# Power_Supply.net
KiCad netlist of a schematic drawn in Altium Designer
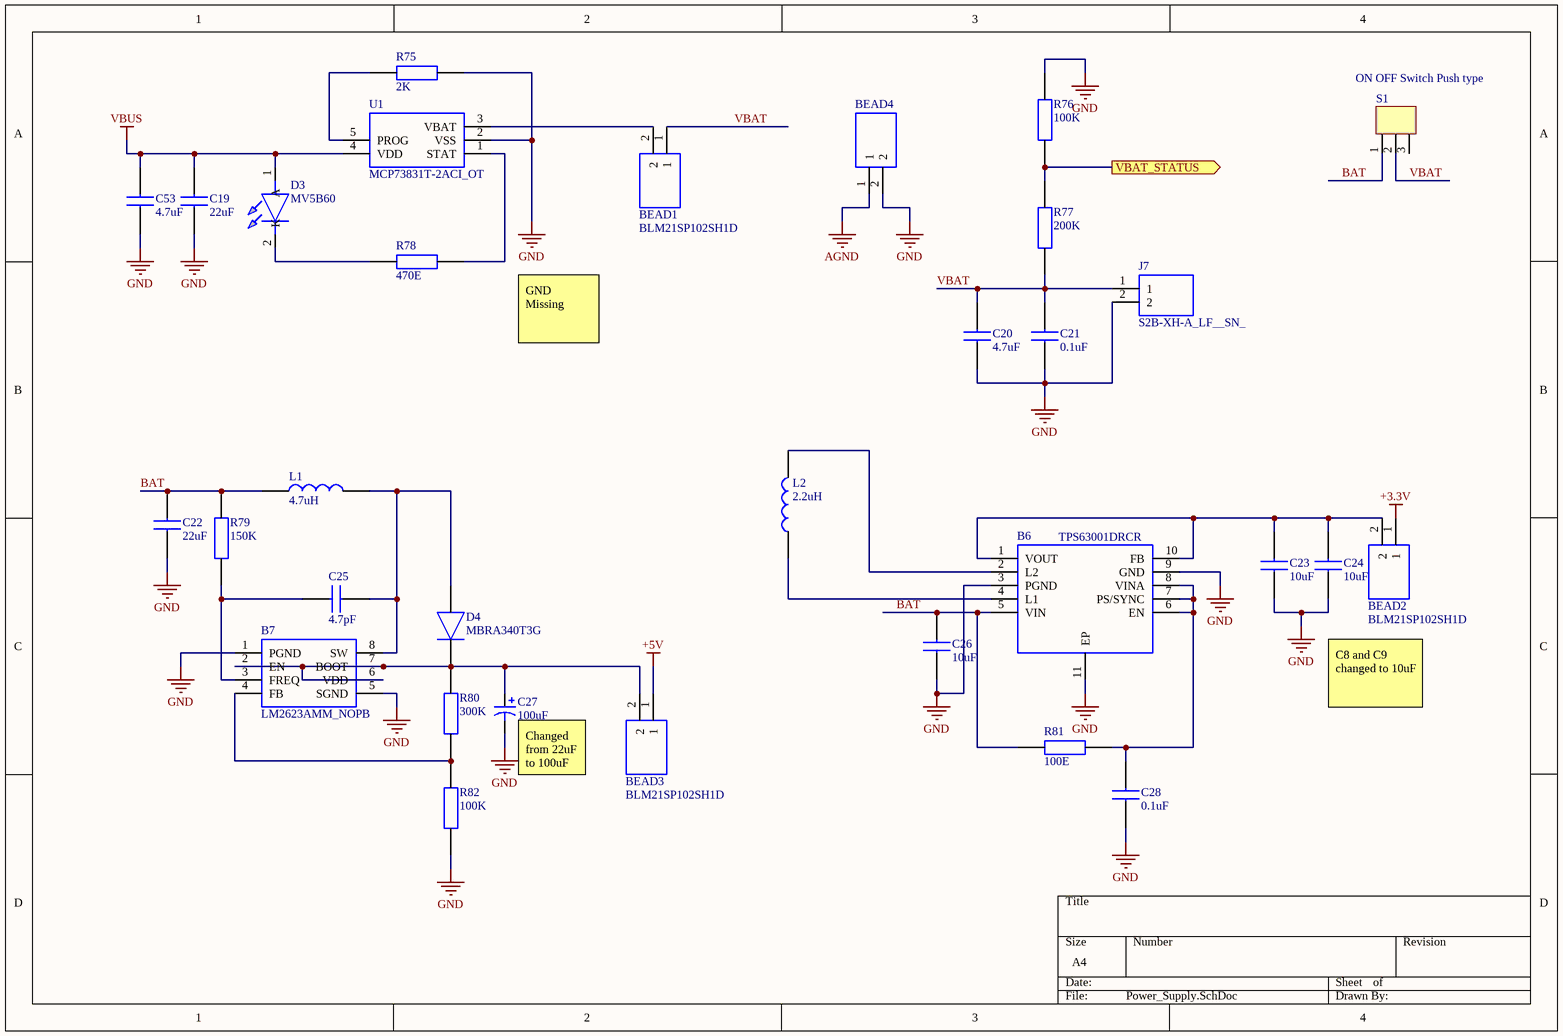
[diagram p0: Power_Supply.SchDoc]

(export (version "E")
  (design (tool "Eeschema 10.0.6"))
  (components
    (comp (ref "B6")
      (value "TPS63001DRCR")
      (footprint "SON50P300X300X100-11N-D")
      (description "96% Buck-Boost Converter with 1.7A Current Switches, 3.3V fixed Output voltage in 3x3 QFN")
      (fields (field (name "MOUSER PART NUMBER") "595-TPS63001DRCR"))
      (libsource (lib "TPS63001DRCR") (part "TPS63001DRCR"))
    )
    (comp (ref "B7")
      (value "LM2623AMM_NOPB")
      (footprint "SOP65P490X110-8N")
      (description "General Purpose, Gated Oscillator Based, DC/DC Boost Converter")
      (fields
        (field (name "MANUFACTURER_PART_NUMBER") "LM2623AMM/NOPB")
        (field (name "MOUSER PART NUMBER") "926-LM2623AMM/NOPB")
      )
      (libsource (lib "LM2623AMM") (part "LM2623AMM_NOPB"))
    )
    (comp (ref "BEAD1")
      (value "BLM21SP102SH1D")
      (footprint "Bead_0805")
      (description "BLM21_H1D Series EMI Suppression Filter 1000+/-25% at 100MHz 1.6A @85")
      (fields (field (name "MOUSER PART NUMBER") "81-BLM21SP102SH1D"))
      (libsource (lib "Bead_0805") (part "BLM21SP102SH1D"))
    )
    (comp (ref "BEAD2")
      (value "BLM21SP102SH1D")
      (footprint "Bead_0805")
      (description "BLM21_H1D Series EMI Suppression Filter 1000+/-25% at 100MHz 1.6A @85")
      (fields (field (name "MOUSER PART NUMBER") "81-BLM21SP102SH1D"))
      (libsource (lib "Bead_0805") (part "BLM21SP102SH1D"))
    )
    (comp (ref "BEAD3")
      (value "BLM21SP102SH1D")
      (footprint "Bead_0805")
      (description "BLM21_H1D Series EMI Suppression Filter 1000+/-25% at 100MHz 1.6A @85")
      (fields (field (name "MOUSER PART NUMBER") "81-BLM21SP102SH1D"))
      (libsource (lib "Bead_0805") (part "BLM21SP102SH1D"))
    )
    (comp (ref "BEAD4")
      (value "BLM21SP102SH1D")
      (footprint "Bead_0805")
      (description "BLM21_H1D Series EMI Suppression Filter 1000+/-25% at 100MHz 1.6A @85")
      (fields (field (name "MOUSER PART NUMBER") "81-BLM21SP102SH1D"))
      (libsource (lib "Bead_0805") (part "BLM21SP102SH1D"))
    )
    (comp (ref "C19")
      (value "22uF")
      (footprint "CAPC3216X180N")
      (description "Multilayer Ceramic Capacitors MLCC - SMD/SMT 22uF 10% 10V")
      (fields
        (field (name "MANUFACTURER_PART_NUMBER") "CC1206KKX7R6BB226")
        (field (name "MOUSER PART NUMBER") "603-CC206KKX7R6BB226")
      )
      (libsource (lib "22uF_1206") (part "CC1206KKX7R6BB226"))
    )
    (comp (ref "C20")
      (value "4.7uF")
      (footprint "CAPC2012X140N")
      (description "KEMET 0805 (2012M) 4.7uF MLCC 6.3V dc +/-5% SMD C0805C475J9RACAUTO")
      (fields
        (field (name "MANUFACTURER_PART_NUMBER") "C0805C475J9RACAUTO")
        (field (name "MOUSER PART NUMBER") "80-C0805C475J9RAUTO")
      )
      (libsource (lib "4.7uF_0805") (part "C0805C475J9RACAUTO"))
    )
    (comp (ref "C21")
      (value "0.1uF")
      (footprint "CAPC1005X55N")
      (description "Multilayer Ceramic Capacitors MLCC - SMD/SMT 16V 0.1uF X7R 0402 20%")
      (fields
        (field (name "MANUFACTURER_PART_NUMBER") "C0402C104M4RECTU")
        (field (name "MOUSER PART NUMBER") "80-C0402C104M4RECTU")
      )
      (libsource (lib "0.1uF_0402") (part "C0402C104M4RECTU"))
    )
    (comp (ref "C22")
      (value "22uF")
      (footprint "CAPC3216X180N")
      (description "Multilayer Ceramic Capacitors MLCC - SMD/SMT 22uF 10% 10V")
      (fields
        (field (name "MANUFACTURER_PART_NUMBER") "CC1206KKX7R6BB226")
        (field (name "MOUSER PART NUMBER") "603-CC206KKX7R6BB226")
      )
      (libsource (lib "22uF_1206") (part "CC1206KKX7R6BB226"))
    )
    (comp (ref "C23")
      (value "10uF")
      (footprint "CAPC1608X80N")
      (description "CAP TANT 10UF 10% 6.3V 1206")
      (fields
        (field (name "MANUFACTURER_PART_NUMBER") "293D106X96R3A2TE3")
        (field (name "ARROW PART NUMBER") "C0402C104M4RECTU")
      )
      (libsource (lib "0.1uF_0402") (part "C0402C104M4RECTU"))
    )
    (comp (ref "C24")
      (value "10uF")
      (footprint "CAPC1608X80N")
      (description "CAP TANT 10UF 10% 6.3V 1206")
      (fields
        (field (name "MANUFACTURER_PART_NUMBER") "293D106X96R3A2TE3")
        (field (name "ARROW PART NUMBER") "CC1206KKX7R6BB226")
      )
      (libsource (lib "22uF_1206") (part "CC1206KKX7R6BB226"))
    )
    (comp (ref "C25")
      (value "4.7pF")
      (footprint "CAPC2012X88N")
      (description "Kemet 0805 C 4.7pF Ceramic Multilayer Capacitor, 200 V dc, +125C, C0G Dielectric, +/-0.25pF")
      (fields
        (field (name "MANUFACTURER_PART_NUMBER") "C0805C479C2GACTU")
        (field (name "MOUSER PART NUMBER") "80-C0805C479C2G")
      )
      (libsource (lib "4.7pF_0805") (part "C0805C479C2GACTU"))
    )
    (comp (ref "C26")
      (value "10uF")
      (footprint "CAPC3216X170N")
      (description "Multilayer Ceramic Capacitors MLCC - SMD/SMT 10uF 25volts 10%")
      (fields
        (field (name "MANUFACTURER_PART_NUMBER") "VJ1206G106KXXTW1BC")
        (field (name "MOUSER PART NUMBER") "77-VJ126G106KXXTW1BC")
      )
      (libsource (lib "10uF_1206") (part "VJ1206G106KXXTW1BC"))
    )
    (comp (ref "C27")
      (value "100uF")
      (footprint "Tantalum Capacitor_2917")
      (description "Polarized Capacitor (Radial)")
      (fields (field (name "Comment") "Cap Pol1") (field (name "PUBLISHER") "Altium Limited"))
      (libsource (lib "Miscellaneous Devices") (part "Cap Pol1"))
    )
    (comp (ref "C28")
      (value "0.1uF")
      (footprint "CAPC1005X55N")
      (description "Multilayer Ceramic Capacitors MLCC - SMD/SMT 16V 0.1uF X7R 0402 20%")
      (fields
        (field (name "MANUFACTURER_PART_NUMBER") "C0402C104M4RECTU")
        (field (name "MOUSER PART NUMBER") "80-C0402C104M4RECTU")
      )
      (libsource (lib "0.1uF_0402") (part "C0402C104M4RECTU"))
    )
    (comp (ref "C53")
      (value "4.7uF")
      (footprint "CAPC2012X140N")
      (description "KEMET 0805 (2012M) 4.7uF MLCC 6.3V dc +/-5% SMD C0805C475J9RACAUTO")
      (fields
        (field (name "MANUFACTURER_PART_NUMBER") "C0805C475J9RACAUTO")
        (field (name "MOUSER PART NUMBER") "80-C0805C475J9RAUTO")
      )
      (libsource (lib "4.7uF_0805") (part "C0805C475J9RACAUTO"))
    )
    (comp (ref "D3")
      (value "MV5B60")
      (footprint "MV5B60")
      (description "Standard LEDs - Through Hole T-100 BLUE CLEAR")
      (fields (field (name "MOUSER PART NUMBER") "638-MV5B60"))
      (libsource (lib "MV5B60") (part "MV5B60"))
    )
    (comp (ref "D4")
      (value "MBRA340T3G")
      (footprint "DIOM5226X220N")
      (description "MBRA340T3G, Schottky Diode,  3A max, 40V, 2-Pin, SMA")
      (fields (field (name "MOUSER PART NUMBER") "863-MBRA340T3G"))
      (libsource (lib "MBRA340T3G") (part "MBRA340T3G"))
    )
    (comp (ref "J7")
      (value "S2B-XH-A_LF__SN_")
      (footprint "SHDRRA2W80P0X250_1X2_740X1150X610P")
      (fields (field (name "MANUFACTURER_PART_NUMBER") "S2B-XH-A(LF)(SN)"))
      (libsource (lib "S2B-XH-A_LF__SN_") (part "S2B-XH-A_LF__SN_"))
    )
    (comp (ref "L1")
      (value "4.7uH")
      (footprint "INDC2012X140N")
      (description "BRC2012T2R2MD")
      (fields (field (name "MOUSER PART NUMBER") "963-BRC2012T2R2MD"))
      (libsource (lib "2.2uH_0805") (part "BRC2012T2R2MD"))
    )
    (comp (ref "L2")
      (value "2.2uH")
      (footprint "INDC2012X140N")
      (description "BRC2012T2R2MD")
      (fields (field (name "MOUSER PART NUMBER") "963-BRC2012T2R2MD"))
      (libsource (lib "2.2uH_0805") (part "BRC2012T2R2MD"))
    )
    (comp (ref "R75")
      (value "2K")
      (footprint "RESC1005X40N")
      (description "RESISTOR, 0402 2K Ohms +/-5% 1/16 W")
      (fields
        (field (name "MANUFACTURER_PART_NUMBER") "RC0402JR-072KL")
        (field (name "MOUSER PART NUMBER") "603-RC0402JR-072KL")
      )
      (libsource (lib "2K_0402") (part "RC0402JR-072KL"))
    )
    (comp (ref "R76")
      (value "100K")
      (footprint "RESC2012X60N")
      (description "Thick Film Resistors - SMD 2M OHM 5%")
      (fields
        (field (name "MANUFACTURER_PART_NUMBER") "RC0805JR-072ML")
        (field (name "MOUSER PART NUMBER") "603-RC0805JR-072ML")
      )
      (libsource (lib "2M_0805") (part "RC0805JR-072ML"))
    )
    (comp (ref "R77")
      (value "200K")
      (footprint "RESC2012X60N")
      (description "Thick Film Resistors - SMD 806K OHM 1%")
      (fields
        (field (name "MANUFACTURER_PART_NUMBER") "RC0805FR-07806KL")
        (field (name "MOUSER PART NUMBER") "603-RC0805FR-07806KL")
      )
      (libsource (lib "806K_0805") (part "RC0805FR-07806KL"))
    )
    (comp (ref "R78")
      (value "470E")
      (footprint "RESC1005X40N")
      (description "Thick Film Resistors - SMD 470 ohm 5% 50V General Purpose")
      (fields
        (field (name "MANUFACTURER_PART_NUMBER") "RC0402JR-13470RL")
        (field (name "MOUSER PART NUMBER") "603-RC0402JR-13470RL")
      )
      (libsource (lib "470E_0402") (part "RC0402JR-13470RL"))
    )
    (comp (ref "R79")
      (value "150K")
      (footprint "RESC2012X50N")
      (description "Thick Film Resistors - SMD 1/8watt 150Kohms .5%")
      (fields
        (field (name "MANUFACTURER_PART_NUMBER") "CRCW0805150KDKTA")
        (field (name "MOUSER PART NUMBER") "71-CRCW08051503DT")
      )
      (libsource (lib "150K_0805") (part "CRCW0805150KDKTA"))
    )
    (comp (ref "R80")
      (value "300K")
      (footprint "RESC1005X40N")
      (description "Thick Film Resistors - SMD 300K Ohm 5% 1/16W 50 Volts")
      (fields
        (field (name "MANUFACTURER_PART_NUMBER") "RC0402JR-07300KL")
        (field (name "MOUSER PART NUMBER") "603-RC0402JR-07300KL")
      )
      (libsource (lib "300K_0402") (part "RC0402JR-07300KL"))
    )
    (comp (ref "R81")
      (value "100E")
      (footprint "RESC1005X40N")
      (description "YAGEO (PHYCOMP) - RC0402FR-07100RL - RES, THICK FILM, 100R, 1%, 0.0625W, 0402")
      (fields
        (field (name "MANUFACTURER_PART_NUMBER") "RC0402FR-07100RL")
        (field (name "MOUSER PART NUMBER") "603-RC0402FR-07100RL")
      )
      (libsource (lib "100E_0402") (part "RC0402FR-07100RL"))
    )
    (comp (ref "R82")
      (value "100K")
      (footprint "RESC1005X40N")
      (description "Thick Film Resistors - SMD .063watt 100kohms 1% 0402 100ppm")
      (fields
        (field (name "MANUFACTURER_PART_NUMBER") "RCG0402100KFKED")
        (field (name "MOUSER PART NUMBER") "71-RCG0402100KFKED")
      )
      (libsource (lib "100K_0402") (part "RCG0402100KFKED"))
    )
    (comp (ref "S1")
      (value "ON OFF Switch Push type")
      (footprint "SPST_Push type")
      (fields (field (name "PART NUMBER") "PN12SHNA03QE"))
      (libsource (lib "CV-R-BAP_V2.1.5") (part "ON OFF Switch Push type"))
    )
    (comp (ref "U1")
      (value "MCP73831T-2ACI_OT")
      (footprint "SOT95P270X145-5N")
      (description "Li-Ion Charge Controller 4.2V SOT23-5")
      (fields
        (field (name "MANUFACTURER_PART_NUMBER") "MCP73831T-2ACI/OT")
        (field (name "MOUSER PART NUMBER") "579-MCP73831T-2ACIOT")
      )
      (libsource (lib "MCP73831T") (part "MCP73831T-2ACI_OT"))
    )
  )
  (nets
    (net (code "1") (name "+3.3V") (class "Default")
      (node (ref "BEAD2") (pin "1") (pinfunction "1_1") (pintype "passive"))
    )
    (net (code "2") (name "+5V") (class "Default")
      (node (ref "BEAD3") (pin "1") (pinfunction "1_1") (pintype "passive"))
    )
    (net (code "3") (name "/BAT") (class "Default")
      (node (ref "B6") (pin "5") (pinfunction "VIN_5") (pintype "passive"))
      (node (ref "C22") (pin "2") (pinfunction "2_2") (pintype "passive"))
      (node (ref "C26") (pin "2") (pinfunction "2_2") (pintype "passive"))
      (node (ref "L1") (pin "1") (pinfunction "1_1") (pintype "passive"))
      (node (ref "R79") (pin "2") (pinfunction "2_2") (pintype "passive"))
      (node (ref "R81") (pin "2") (pinfunction "2_2") (pintype "passive"))
      (node (ref "S1") (pin "1") (pinfunction "1_1") (pintype "passive"))
    )
    (net (code "4") (name "/VBAT") (class "Default")
      (node (ref "BEAD1") (pin "1") (pinfunction "1_1") (pintype "passive"))
      (node (ref "C20") (pin "2") (pinfunction "2_2") (pintype "passive"))
      (node (ref "C21") (pin "2") (pinfunction "2_2") (pintype "passive"))
      (node (ref "J7") (pin "1") (pinfunction "1_1") (pintype "passive"))
      (node (ref "R77") (pin "1") (pinfunction "1_1") (pintype "passive"))
      (node (ref "S1") (pin "2") (pinfunction "2_2") (pintype "passive"))
    )
    (net (code "5") (name "/VBAT_STATUS") (class "Default")
      (node (ref "R76") (pin "1") (pinfunction "1_1") (pintype "passive"))
      (node (ref "R77") (pin "2") (pinfunction "2_2") (pintype "passive"))
    )
    (net (code "6") (name "AGND") (class "Default")
      (node (ref "BEAD4") (pin "1") (pinfunction "1_1") (pintype "passive"))
    )
    (net (code "7") (name "GND") (class "Default")
      (node (ref "B6") (pin "11") (pinfunction "EP_11") (pintype "passive"))
      (node (ref "B6") (pin "3") (pinfunction "PGND_3") (pintype "passive"))
      (node (ref "B6") (pin "9") (pinfunction "GND_9") (pintype "passive"))
      (node (ref "B7") (pin "1") (pinfunction "PGND_1") (pintype "passive"))
      (node (ref "B7") (pin "5") (pinfunction "SGND_5") (pintype "passive"))
      (node (ref "BEAD4") (pin "2") (pinfunction "2_2") (pintype "passive"))
      (node (ref "C19") (pin "1") (pinfunction "1_1") (pintype "passive"))
      (node (ref "C20") (pin "1") (pinfunction "1_1") (pintype "passive"))
      (node (ref "C21") (pin "1") (pinfunction "1_1") (pintype "passive"))
      (node (ref "C22") (pin "1") (pinfunction "1_1") (pintype "passive"))
      (node (ref "C23") (pin "1") (pinfunction "1_1") (pintype "passive"))
      (node (ref "C24") (pin "1") (pinfunction "1_1") (pintype "passive"))
      (node (ref "C26") (pin "1") (pinfunction "1_1") (pintype "passive"))
      (node (ref "C27") (pin "2") (pinfunction "2_2") (pintype "passive"))
      (node (ref "C28") (pin "1") (pinfunction "1_1") (pintype "passive"))
      (node (ref "C53") (pin "1") (pinfunction "1_1") (pintype "passive"))
      (node (ref "J7") (pin "2") (pinfunction "2_2") (pintype "passive"))
      (node (ref "R75") (pin "2") (pinfunction "2_2") (pintype "passive"))
      (node (ref "R76") (pin "2") (pinfunction "2_2") (pintype "passive"))
      (node (ref "R82") (pin "1") (pinfunction "1_1") (pintype "passive"))
      (node (ref "U1") (pin "2") (pinfunction "VSS_2") (pintype "passive"))
    )
    (net (code "8") (name "Net-(B6-EN)") (class "Default")
      (node (ref "B6") (pin "6") (pinfunction "EN_6") (pintype "passive"))
      (node (ref "B6") (pin "7") (pinfunction "PS/SYNC_7") (pintype "passive"))
      (node (ref "B6") (pin "8") (pinfunction "VINA_8") (pintype "passive"))
      (node (ref "C28") (pin "2") (pinfunction "2_2") (pintype "passive"))
      (node (ref "R81") (pin "1") (pinfunction "1_1") (pintype "passive"))
    )
    (net (code "9") (name "Net-(B6-FB)") (class "Default")
      (node (ref "B6") (pin "1") (pinfunction "VOUT_1") (pintype "passive"))
      (node (ref "B6") (pin "10") (pinfunction "FB_10") (pintype "passive"))
      (node (ref "BEAD2") (pin "2") (pinfunction "2_2") (pintype "passive"))
      (node (ref "C23") (pin "2") (pinfunction "2_2") (pintype "passive"))
      (node (ref "C24") (pin "2") (pinfunction "2_2") (pintype "passive"))
    )
    (net (code "10") (name "Net-(B6-L1)") (class "Default")
      (node (ref "B6") (pin "4") (pinfunction "L1_4") (pintype "passive"))
      (node (ref "L2") (pin "1") (pinfunction "1_1") (pintype "passive"))
    )
    (net (code "11") (name "Net-(B6-L2)") (class "Default")
      (node (ref "B6") (pin "2") (pinfunction "L2_2") (pintype "passive"))
      (node (ref "L2") (pin "2") (pinfunction "2_2") (pintype "passive"))
    )
    (net (code "12") (name "Net-(B7-BOOT)") (class "Default")
      (node (ref "B7") (pin "2") (pinfunction "EN_2") (pintype "passive"))
      (node (ref "B7") (pin "6") (pinfunction "VDD_6") (pintype "passive"))
      (node (ref "B7") (pin "7") (pinfunction "BOOT_7") (pintype "passive"))
      (node (ref "BEAD3") (pin "2") (pinfunction "2_2") (pintype "passive"))
      (node (ref "C27") (pin "1") (pinfunction "1_1") (pintype "passive"))
      (node (ref "D4") (pin "1") (pinfunction "K_1") (pintype "passive"))
      (node (ref "R80") (pin "2") (pinfunction "2_2") (pintype "passive"))
    )
    (net (code "13") (name "Net-(B7-FB)") (class "Default")
      (node (ref "B7") (pin "4") (pinfunction "FB_4") (pintype "passive"))
      (node (ref "R80") (pin "1") (pinfunction "1_1") (pintype "passive"))
      (node (ref "R82") (pin "2") (pinfunction "2_2") (pintype "passive"))
    )
    (net (code "14") (name "Net-(B7-FREQ)") (class "Default")
      (node (ref "B7") (pin "3") (pinfunction "FREQ_3") (pintype "passive"))
      (node (ref "C25") (pin "1") (pinfunction "1_1") (pintype "passive"))
      (node (ref "R79") (pin "1") (pinfunction "1_1") (pintype "passive"))
    )
    (net (code "15") (name "Net-(B7-SW)") (class "Default")
      (node (ref "B7") (pin "8") (pinfunction "SW_8") (pintype "passive"))
      (node (ref "C25") (pin "2") (pinfunction "2_2") (pintype "passive"))
      (node (ref "D4") (pin "2") (pinfunction "A_2") (pintype "passive"))
      (node (ref "L1") (pin "2") (pinfunction "2_2") (pintype "passive"))
    )
    (net (code "16") (name "Net-(D3-K)") (class "Default")
      (node (ref "D3") (pin "2") (pinfunction "K_2") (pintype "passive"))
      (node (ref "R78") (pin "2") (pinfunction "2_2") (pintype "passive"))
    )
    (net (code "17") (name "Net-(U1-PROG)") (class "Default")
      (node (ref "R75") (pin "1") (pinfunction "1_1") (pintype "passive"))
      (node (ref "U1") (pin "5") (pinfunction "PROG_5") (pintype "passive"))
    )
    (net (code "18") (name "Net-(U1-STAT)") (class "Default")
      (node (ref "R78") (pin "1") (pinfunction "1_1") (pintype "passive"))
      (node (ref "U1") (pin "1") (pinfunction "STAT_1") (pintype "passive"))
    )
    (net (code "19") (name "Net-(U1-VBAT)") (class "Default")
      (node (ref "BEAD1") (pin "2") (pinfunction "2_2") (pintype "passive"))
      (node (ref "U1") (pin "3") (pinfunction "VBAT_3") (pintype "passive"))
    )
    (net (code "20") (name "VBUS") (class "Default")
      (node (ref "C19") (pin "2") (pinfunction "2_2") (pintype "passive"))
      (node (ref "C53") (pin "2") (pinfunction "2_2") (pintype "passive"))
      (node (ref "D3") (pin "1") (pinfunction "A_1") (pintype "passive"))
      (node (ref "U1") (pin "4") (pinfunction "VDD_4") (pintype "passive"))
    )
    (net (code "21") (name "unconnected-(S1-Pad3)") (class "Default")
      (node (ref "S1") (pin "3") (pinfunction "3_3") (pintype "passive"))
    )
  )
)
